# Sheet1.net
KiCad netlist of a schematic drawn in Altium Designer
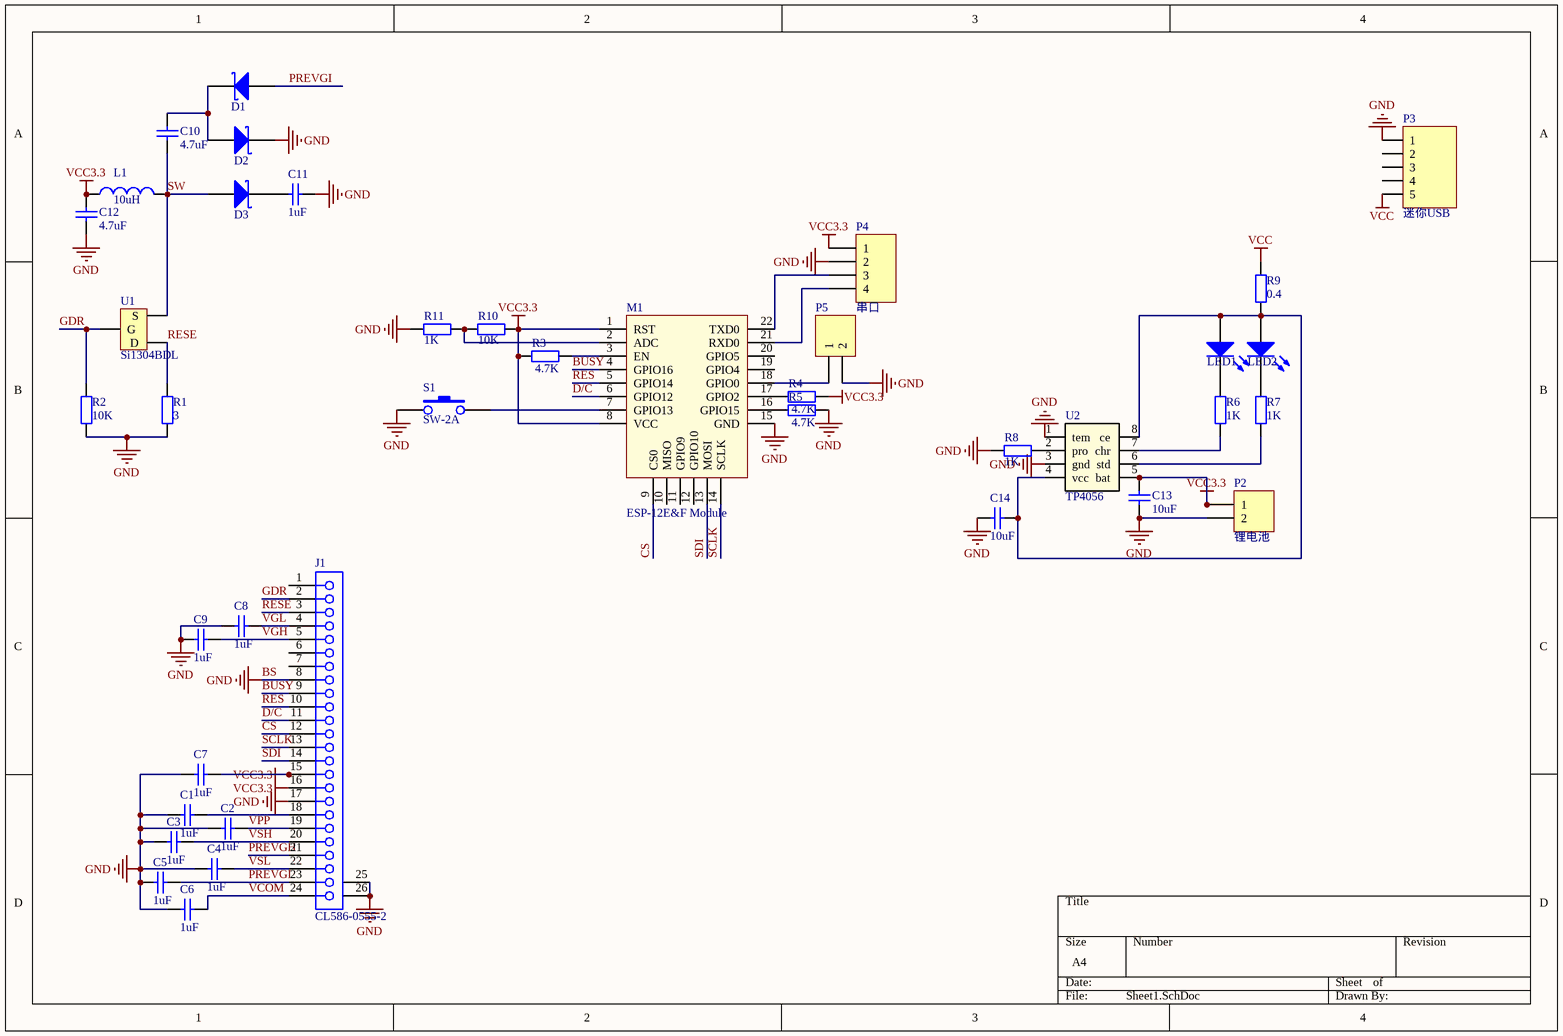
[diagram p0: Sheet1.SchDoc]

(export (version "E")
  (design (tool "Eeschema 10.0.6"))
  (components
    (comp (ref "C1")
      (value "1uF")
      (footprint "0805C")
      (description "Capacitor")
      (fields (field (name "Comment") "无极性电容") (field (name "PUBLISHER") "Altium Limited"))
      (libsource (lib "Integrated_Library1") (part "无极性电容"))
    )
    (comp (ref "C2")
      (value "1uF")
      (footprint "0805C")
      (description "Capacitor")
      (fields (field (name "Comment") "无极性电容") (field (name "PUBLISHER") "Altium Limited"))
      (libsource (lib "Integrated_Library1") (part "无极性电容"))
    )
    (comp (ref "C3")
      (value "1uF")
      (footprint "0805C")
      (description "Capacitor")
      (fields (field (name "Comment") "无极性电容") (field (name "PUBLISHER") "Altium Limited"))
      (libsource (lib "Integrated_Library1") (part "无极性电容"))
    )
    (comp (ref "C4")
      (value "1uF")
      (footprint "0805C")
      (description "Capacitor")
      (fields (field (name "Comment") "无极性电容") (field (name "PUBLISHER") "Altium Limited"))
      (libsource (lib "Integrated_Library1") (part "无极性电容"))
    )
    (comp (ref "C5")
      (value "1uF")
      (footprint "0805C")
      (description "Capacitor")
      (fields (field (name "Comment") "无极性电容") (field (name "PUBLISHER") "Altium Limited"))
      (libsource (lib "Integrated_Library1") (part "无极性电容"))
    )
    (comp (ref "C6")
      (value "1uF")
      (footprint "0805C")
      (description "Capacitor")
      (fields (field (name "Comment") "无极性电容") (field (name "PUBLISHER") "Altium Limited"))
      (libsource (lib "Integrated_Library1") (part "无极性电容"))
    )
    (comp (ref "C7")
      (value "1uF")
      (footprint "0805C")
      (description "Capacitor")
      (fields (field (name "Comment") "无极性电容") (field (name "PUBLISHER") "Altium Limited"))
      (libsource (lib "Integrated_Library1") (part "无极性电容"))
    )
    (comp (ref "C8")
      (value "1uF")
      (footprint "0805C")
      (description "Capacitor")
      (fields (field (name "Comment") "无极性电容") (field (name "PUBLISHER") "Altium Limited"))
      (libsource (lib "Integrated_Library1") (part "无极性电容"))
    )
    (comp (ref "C9")
      (value "1uF")
      (footprint "0805C")
      (description "Capacitor")
      (fields (field (name "Comment") "无极性电容") (field (name "PUBLISHER") "Altium Limited"))
      (libsource (lib "Integrated_Library1") (part "无极性电容"))
    )
    (comp (ref "C10")
      (value "4.7uF")
      (footprint "0805C")
      (description "Capacitor")
      (fields (field (name "Comment") "无极性电容") (field (name "PUBLISHER") "Altium Limited"))
      (libsource (lib "Integrated_Library1") (part "无极性电容"))
    )
    (comp (ref "C11")
      (value "1uF")
      (footprint "0805C")
      (description "Capacitor")
      (fields (field (name "Comment") "无极性电容") (field (name "PUBLISHER") "Altium Limited"))
      (libsource (lib "Integrated_Library1") (part "无极性电容"))
    )
    (comp (ref "C12")
      (value "4.7uF")
      (footprint "0805C")
      (description "Capacitor")
      (fields (field (name "Comment") "无极性电容") (field (name "PUBLISHER") "Altium Limited"))
      (libsource (lib "Integrated_Library1") (part "无极性电容"))
    )
    (comp (ref "C13")
      (value "10uF")
      (footprint "0805C")
      (description "Capacitor")
      (fields (field (name "Comment") "无极性电容") (field (name "PUBLISHER") "Altium Limited"))
      (libsource (lib "Integrated_Library1") (part "无极性电容"))
    )
    (comp (ref "C14")
      (value "10uF")
      (footprint "0805C")
      (description "Capacitor")
      (fields (field (name "Comment") "无极性电容") (field (name "PUBLISHER") "Altium Limited"))
      (libsource (lib "Integrated_Library1") (part "无极性电容"))
    )
    (comp (ref "D1")
      (value "1N5817-肖特基二极管_1")
      (footprint "SOD123")
      (libsource (lib "Integrated_Library1") (part "1N5817-肖特基二极管_1"))
    )
    (comp (ref "D2")
      (value "1N5817-肖特基二极管_1")
      (footprint "SOD123")
      (libsource (lib "Integrated_Library1") (part "1N5817-肖特基二极管_1"))
    )
    (comp (ref "D3")
      (value "1N5817-肖特基二极管_1")
      (footprint "SOD123")
      (libsource (lib "Integrated_Library1") (part "1N5817-肖特基二极管_1"))
    )
    (comp (ref "J1")
      (value "CL586-0555-2")
      (footprint "FH12-24S-0.5SH")
      (description "FH12 Series, \"Flip-Lock\" SMT/ZIF Connector - 0.5mm Spaced Top Contact")
      (fields (field (name "PUBLISHER") "Altium Limited"))
      (libsource (lib "HRS FPC-FFC FH12 Series") (part "CL586-0555-2"))
    )
    (comp (ref "L1")
      (value "10uH")
      (footprint "CAPM-B-3528X21N")
      (description "Inductor")
      (fields (field (name "PUBLISHER") "Altium Limited"))
      (libsource (lib "Integrated_Library1") (part "Inductor"))
    )
    (comp (ref "LED1")
      (value "LED-贴片-直插")
      (footprint "LED_0805")
      (libsource (lib "Integrated_Library1") (part "LED-贴片-直插"))
    )
    (comp (ref "LED2")
      (value "LED-贴片-直插")
      (footprint "LED_0805")
      (libsource (lib "Integrated_Library1") (part "LED-贴片-直插"))
    )
    (comp (ref "M1")
      (value "ESP-12E&F Module")
      (footprint "ESP-12E&F Module")
      (libsource (lib "ESP-12E&F Module") (part "ESP-12E&F Module"))
    )
    (comp (ref "P2")
      (value "锂电池")
      (footprint "HDR1X2")
      (description "Header, 2-Pin")
      (fields (field (name "PUBLISHER") "Altium Limited"))
      (libsource (lib "Miscellaneous Connectors") (part "Header 2"))
    )
    (comp (ref "P3") (value "迷你USB") (footprint "迷你usb") (libsource (lib "wodeku") (part "迷你USB")))
    (comp (ref "P4")
      (value "串口")
      (footprint "HDR1X4")
      (description "Header, 4-Pin")
      (fields (field (name "PUBLISHER") "Altium Limited"))
      (libsource (lib "Miscellaneous Connectors") (part "Header 4"))
    )
    (comp (ref "P5")
      (value "~")
      (footprint "HDR1X2")
      (description "Header, 2-Pin")
      (fields (field (name "PUBLISHER") "Altium Limited"))
      (libsource (lib "") (part "Header 2_1"))
    )
    (comp (ref "R1")
      (value "3")
      (footprint "0805R")
      (description "Resistor")
      (fields (field (name "Comment") "贴片电阻") (field (name "PUBLISHER") "Altium Limited"))
      (libsource (lib "") (part "贴片电阻_3"))
    )
    (comp (ref "R2")
      (value "10K")
      (footprint "0805R")
      (description "Resistor")
      (fields (field (name "Comment") "贴片电阻") (field (name "PUBLISHER") "Altium Limited"))
      (libsource (lib "") (part "贴片电阻_3"))
    )
    (comp (ref "R3")
      (value "4.7K")
      (footprint "0805R")
      (description "Resistor")
      (fields (field (name "Comment") "贴片电阻") (field (name "PUBLISHER") "Altium Limited"))
      (libsource (lib "Integrated_Library1") (part "贴片电阻"))
    )
    (comp (ref "R4")
      (value "4.7K")
      (footprint "0805R")
      (description "Resistor")
      (fields (field (name "Comment") "贴片电阻") (field (name "PUBLISHER") "Altium Limited"))
      (libsource (lib "Integrated_Library1") (part "贴片电阻"))
    )
    (comp (ref "R5")
      (value "4.7K")
      (footprint "0805R")
      (description "Resistor")
      (fields (field (name "Comment") "贴片电阻") (field (name "PUBLISHER") "Altium Limited"))
      (libsource (lib "Integrated_Library1") (part "贴片电阻"))
    )
    (comp (ref "R6")
      (value "1K")
      (footprint "0805R")
      (description "Resistor")
      (fields (field (name "Comment") "贴片电阻") (field (name "PUBLISHER") "Altium Limited"))
      (libsource (lib "") (part "贴片电阻_2"))
    )
    (comp (ref "R7")
      (value "1K")
      (footprint "0805R")
      (description "Resistor")
      (fields (field (name "Comment") "贴片电阻") (field (name "PUBLISHER") "Altium Limited"))
      (libsource (lib "") (part "贴片电阻_2"))
    )
    (comp (ref "R8")
      (value "1K")
      (footprint "0805R")
      (description "Resistor")
      (fields (field (name "Comment") "贴片电阻") (field (name "PUBLISHER") "Altium Limited"))
      (libsource (lib "") (part "贴片电阻_1"))
    )
    (comp (ref "R9")
      (value "0.4")
      (footprint "0805R")
      (description "Resistor")
      (fields (field (name "Comment") "贴片电阻") (field (name "PUBLISHER") "Altium Limited"))
      (libsource (lib "") (part "贴片电阻_3"))
    )
    (comp (ref "R10")
      (value "10K")
      (footprint "0805R")
      (description "Resistor")
      (fields (field (name "Comment") "贴片电阻") (field (name "PUBLISHER") "Altium Limited"))
      (libsource (lib "") (part "贴片电阻_1"))
    )
    (comp (ref "R11")
      (value "1K")
      (footprint "0805R")
      (description "Resistor")
      (fields (field (name "Comment") "贴片电阻") (field (name "PUBLISHER") "Altium Limited"))
      (libsource (lib "") (part "贴片电阻_1"))
    )
    (comp (ref "S1")
      (value "SW-2A")
      (footprint "SW贴片-3*6*2.5")
      (libsource (lib "Integrated_Library1") (part "SW-2A"))
    )
    (comp (ref "U1") (value "Si1304BDL") (footprint "AO3400") (libsource (lib "wodeku") (part "AO3400")))
    (comp (ref "U2") (value "TP4056") (footprint "SOP8LM386") (libsource (lib "TP4056") (part "TP4056")))
  )
  (nets
    (net (code "1") (name "/BUSY") (class "Default")
      (node (ref "J1") (pin "9") (pinfunction "9_9") (pintype "passive"))
      (node (ref "M1") (pin "4") (pinfunction "GPIO16_4") (pintype "passive"))
    )
    (net (code "2") (name "/CS") (class "Default")
      (node (ref "J1") (pin "12") (pinfunction "12_12") (pintype "passive"))
      (node (ref "M1") (pin "9") (pinfunction "CS0_9") (pintype "passive"))
    )
    (net (code "3") (name "/D{slash}C") (class "Default")
      (node (ref "J1") (pin "11") (pinfunction "11_11") (pintype "passive"))
      (node (ref "M1") (pin "6") (pinfunction "GPIO12_6") (pintype "passive"))
    )
    (net (code "4") (name "/GDR") (class "Default")
      (node (ref "J1") (pin "2") (pinfunction "2_2") (pintype "passive"))
      (node (ref "R2") (pin "2") (pinfunction "2_2") (pintype "passive"))
      (node (ref "U1") (pin "1") (pinfunction "G_1") (pintype "passive"))
    )
    (net (code "5") (name "/PREVGH") (class "Default")
      (node (ref "J1") (pin "21") (pinfunction "21_21") (pintype "passive"))
    )
    (net (code "6") (name "/PREVGI") (class "Default")
      (node (ref "C5") (pin "2") (pinfunction "2_2") (pintype "passive"))
      (node (ref "D1") (pin "1") (pinfunction "A_1") (pintype "passive"))
      (node (ref "J1") (pin "23") (pinfunction "23_23") (pintype "passive"))
    )
    (net (code "7") (name "/RES") (class "Default")
      (node (ref "J1") (pin "10") (pinfunction "10_10") (pintype "passive"))
      (node (ref "M1") (pin "5") (pinfunction "GPIO14_5") (pintype "passive"))
    )
    (net (code "8") (name "/RESE") (class "Default")
      (node (ref "J1") (pin "3") (pinfunction "3_3") (pintype "passive"))
      (node (ref "R1") (pin "2") (pinfunction "2_2") (pintype "passive"))
      (node (ref "U1") (pin "3") (pinfunction "D_3") (pintype "passive"))
    )
    (net (code "9") (name "/SCLK") (class "Default")
      (node (ref "J1") (pin "13") (pinfunction "13_13") (pintype "passive"))
      (node (ref "M1") (pin "14") (pinfunction "SCLK_14") (pintype "passive"))
    )
    (net (code "10") (name "/SDI") (class "Default")
      (node (ref "J1") (pin "14") (pinfunction "14_14") (pintype "passive"))
      (node (ref "M1") (pin "13") (pinfunction "MOSI_13") (pintype "passive"))
    )
    (net (code "11") (name "/SW") (class "Default")
      (node (ref "C10") (pin "1") (pinfunction "1_1") (pintype "passive"))
      (node (ref "D3") (pin "1") (pinfunction "A_1") (pintype "passive"))
      (node (ref "L1") (pin "2") (pinfunction "2_2") (pintype "passive"))
      (node (ref "U1") (pin "2") (pinfunction "S_2") (pintype "passive"))
    )
    (net (code "12") (name "/VCOM") (class "Default")
      (node (ref "C6") (pin "2") (pinfunction "2_2") (pintype "passive"))
      (node (ref "J1") (pin "24") (pinfunction "24_24") (pintype "passive"))
    )
    (net (code "13") (name "/VGH") (class "Default")
      (node (ref "C9") (pin "2") (pinfunction "2_2") (pintype "passive"))
      (node (ref "J1") (pin "5") (pinfunction "5_5") (pintype "passive"))
    )
    (net (code "14") (name "/VGL") (class "Default")
      (node (ref "C8") (pin "2") (pinfunction "2_2") (pintype "passive"))
      (node (ref "J1") (pin "4") (pinfunction "4_4") (pintype "passive"))
    )
    (net (code "15") (name "/VPP") (class "Default")
      (node (ref "C2") (pin "2") (pinfunction "2_2") (pintype "passive"))
      (node (ref "J1") (pin "19") (pinfunction "19_19") (pintype "passive"))
    )
    (net (code "16") (name "/VSH") (class "Default")
      (node (ref "C3") (pin "2") (pinfunction "2_2") (pintype "passive"))
      (node (ref "J1") (pin "20") (pinfunction "20_20") (pintype "passive"))
    )
    (net (code "17") (name "/VSL") (class "Default")
      (node (ref "C4") (pin "2") (pinfunction "2_2") (pintype "passive"))
      (node (ref "J1") (pin "22") (pinfunction "22_22") (pintype "passive"))
    )
    (net (code "18") (name "GND") (class "Default")
      (node (ref "C1") (pin "1") (pinfunction "1_1") (pintype "passive"))
      (node (ref "C11") (pin "1") (pinfunction "1_1") (pintype "passive"))
      (node (ref "C12") (pin "1") (pinfunction "1_1") (pintype "passive"))
      (node (ref "C13") (pin "1") (pinfunction "1_1") (pintype "passive"))
      (node (ref "C14") (pin "2") (pinfunction "2_2") (pintype "passive"))
      (node (ref "C2") (pin "1") (pinfunction "1_1") (pintype "passive"))
      (node (ref "C3") (pin "1") (pinfunction "1_1") (pintype "passive"))
      (node (ref "C4") (pin "1") (pinfunction "1_1") (pintype "passive"))
      (node (ref "C5") (pin "1") (pinfunction "1_1") (pintype "passive"))
      (node (ref "C6") (pin "1") (pinfunction "1_1") (pintype "passive"))
      (node (ref "C7") (pin "1") (pinfunction "1_1") (pintype "passive"))
      (node (ref "C8") (pin "1") (pinfunction "1_1") (pintype "passive"))
      (node (ref "C9") (pin "1") (pinfunction "1_1") (pintype "passive"))
      (node (ref "D2") (pin "2") (pinfunction "K_2") (pintype "passive"))
      (node (ref "J1") (pin "17") (pinfunction "17_17") (pintype "passive"))
      (node (ref "J1") (pin "25") (pinfunction "MH1_25") (pintype "passive"))
      (node (ref "J1") (pin "26") (pinfunction "MH2_26") (pintype "passive"))
      (node (ref "J1") (pin "8") (pinfunction "8_8") (pintype "passive"))
      (node (ref "M1") (pin "15") (pinfunction "GND_15") (pintype "passive"))
      (node (ref "P2") (pin "2") (pinfunction "2_2") (pintype "passive"))
      (node (ref "P3") (pin "1") (pinfunction "1_1") (pintype "passive"))
      (node (ref "P4") (pin "2") (pinfunction "2_2") (pintype "passive"))
      (node (ref "P5") (pin "2") (pinfunction "2_2") (pintype "passive"))
      (node (ref "R1") (pin "1") (pinfunction "1_1") (pintype "passive"))
      (node (ref "R11") (pin "1") (pinfunction "1_1") (pintype "passive"))
      (node (ref "R2") (pin "1") (pinfunction "1_1") (pintype "passive"))
      (node (ref "R5") (pin "1") (pinfunction "1_1") (pintype "passive"))
      (node (ref "R8") (pin "1") (pinfunction "1_1") (pintype "passive"))
      (node (ref "S1") (pin "1") (pinfunction "1_1") (pintype "passive"))
      (node (ref "U2") (pin "1") (pinfunction "tem_1") (pintype "passive"))
      (node (ref "U2") (pin "3") (pinfunction "gnd_3") (pintype "passive"))
    )
    (net (code "19") (name "Net-(C1-Pad2)") (class "Default")
      (node (ref "C1") (pin "2") (pinfunction "2_2") (pintype "passive"))
      (node (ref "J1") (pin "18") (pinfunction "18_18") (pintype "passive"))
    )
    (net (code "20") (name "Net-(D1-K)") (class "Default")
      (node (ref "C10") (pin "2") (pinfunction "2_2") (pintype "passive"))
      (node (ref "D1") (pin "2") (pinfunction "K_2") (pintype "passive"))
      (node (ref "D2") (pin "1") (pinfunction "A_1") (pintype "passive"))
    )
    (net (code "21") (name "Net-(D3-K)") (class "Default")
      (node (ref "C11") (pin "2") (pinfunction "2_2") (pintype "passive"))
      (node (ref "D3") (pin "2") (pinfunction "K_2") (pintype "passive"))
    )
    (net (code "22") (name "Net-(LED1-A)") (class "Default")
      (node (ref "C14") (pin "1") (pinfunction "1_1") (pintype "passive"))
      (node (ref "LED1") (pin "1") (pinfunction "A_1") (pintype "passive"))
      (node (ref "LED2") (pin "1") (pinfunction "A_1") (pintype "passive"))
      (node (ref "R9") (pin "1") (pinfunction "1_1") (pintype "passive"))
      (node (ref "U2") (pin "4") (pinfunction "vcc_4") (pintype "passive"))
      (node (ref "U2") (pin "8") (pinfunction "ce_8") (pintype "passive"))
    )
    (net (code "23") (name "Net-(LED1-K)") (class "Default")
      (node (ref "LED1") (pin "2") (pinfunction "K_2") (pintype "passive"))
      (node (ref "R6") (pin "1") (pinfunction "1_1") (pintype "passive"))
    )
    (net (code "24") (name "Net-(LED2-K)") (class "Default")
      (node (ref "LED2") (pin "2") (pinfunction "K_2") (pintype "passive"))
      (node (ref "R7") (pin "1") (pinfunction "1_1") (pintype "passive"))
    )
    (net (code "25") (name "Net-(M1-ADC)") (class "Default")
      (node (ref "M1") (pin "2") (pinfunction "ADC_2") (pintype "passive"))
      (node (ref "R10") (pin "1") (pinfunction "1_1") (pintype "passive"))
      (node (ref "R11") (pin "2") (pinfunction "2_2") (pintype "passive"))
    )
    (net (code "26") (name "Net-(M1-EN)") (class "Default")
      (node (ref "M1") (pin "3") (pinfunction "EN_3") (pintype "passive"))
      (node (ref "R3") (pin "1") (pinfunction "1_1") (pintype "passive"))
    )
    (net (code "27") (name "Net-(M1-GPIO0)") (class "Default")
      (node (ref "M1") (pin "18") (pinfunction "GPIO0_18") (pintype "passive"))
      (node (ref "P5") (pin "1") (pinfunction "1_1") (pintype "passive"))
    )
    (net (code "28") (name "Net-(M1-GPIO2)") (class "Default")
      (node (ref "M1") (pin "17") (pinfunction "GPIO2_17") (pintype "passive"))
      (node (ref "R4") (pin "2") (pinfunction "2_2") (pintype "passive"))
    )
    (net (code "29") (name "Net-(M1-GPIO13)") (class "Default")
      (node (ref "M1") (pin "7") (pinfunction "GPIO13_7") (pintype "passive"))
      (node (ref "S1") (pin "2") (pinfunction "2_2") (pintype "passive"))
    )
    (net (code "30") (name "Net-(M1-GPIO15)") (class "Default")
      (node (ref "M1") (pin "16") (pinfunction "GPIO15_16") (pintype "passive"))
      (node (ref "R5") (pin "2") (pinfunction "2_2") (pintype "passive"))
    )
    (net (code "31") (name "Net-(M1-RXD0)") (class "Default")
      (node (ref "M1") (pin "21") (pinfunction "RXD0_21") (pintype "passive"))
      (node (ref "P4") (pin "4") (pinfunction "4_4") (pintype "passive"))
    )
    (net (code "32") (name "Net-(M1-TXD0)") (class "Default")
      (node (ref "M1") (pin "22") (pinfunction "TXD0_22") (pintype "passive"))
      (node (ref "P4") (pin "3") (pinfunction "3_3") (pintype "passive"))
    )
    (net (code "33") (name "Net-(U2-chr)") (class "Default")
      (node (ref "R6") (pin "2") (pinfunction "2_2") (pintype "passive"))
      (node (ref "U2") (pin "7") (pinfunction "chr_7") (pintype "passive"))
    )
    (net (code "34") (name "Net-(U2-pro)") (class "Default")
      (node (ref "R8") (pin "2") (pinfunction "2_2") (pintype "passive"))
      (node (ref "U2") (pin "2") (pinfunction "pro_2") (pintype "passive"))
    )
    (net (code "35") (name "Net-(U2-std)") (class "Default")
      (node (ref "R7") (pin "2") (pinfunction "2_2") (pintype "passive"))
      (node (ref "U2") (pin "6") (pinfunction "std_6") (pintype "passive"))
    )
    (net (code "36") (name "VCC") (class "Default")
      (node (ref "P3") (pin "5") (pinfunction "5_5") (pintype "passive"))
      (node (ref "R9") (pin "2") (pinfunction "2_2") (pintype "passive"))
    )
    (net (code "37") (name "VCC3.3") (class "Default")
      (node (ref "C12") (pin "2") (pinfunction "2_2") (pintype "passive"))
      (node (ref "C13") (pin "2") (pinfunction "2_2") (pintype "passive"))
      (node (ref "C7") (pin "2") (pinfunction "2_2") (pintype "passive"))
      (node (ref "J1") (pin "15") (pinfunction "15_15") (pintype "passive"))
      (node (ref "J1") (pin "16") (pinfunction "16_16") (pintype "passive"))
      (node (ref "L1") (pin "1") (pinfunction "1_1") (pintype "passive"))
      (node (ref "M1") (pin "1") (pinfunction "RST_1") (pintype "passive"))
      (node (ref "M1") (pin "8") (pinfunction "VCC_8") (pintype "passive"))
      (node (ref "P2") (pin "1") (pinfunction "1_1") (pintype "passive"))
      (node (ref "P4") (pin "1") (pinfunction "1_1") (pintype "passive"))
      (node (ref "R10") (pin "2") (pinfunction "2_2") (pintype "passive"))
      (node (ref "R3") (pin "2") (pinfunction "2_2") (pintype "passive"))
      (node (ref "R4") (pin "1") (pinfunction "1_1") (pintype "passive"))
      (node (ref "U2") (pin "5") (pinfunction "bat_5") (pintype "passive"))
    )
    (net (code "38") (name "unconnected-(J1-Pad1)") (class "Default")
      (node (ref "J1") (pin "1") (pinfunction "1_1") (pintype "passive"))
    )
    (net (code "39") (name "unconnected-(J1-Pad6)") (class "Default")
      (node (ref "J1") (pin "6") (pinfunction "6_6") (pintype "passive"))
    )
    (net (code "40") (name "unconnected-(J1-Pad7)") (class "Default")
      (node (ref "J1") (pin "7") (pinfunction "7_7") (pintype "passive"))
    )
    (net (code "41") (name "unconnected-(M1-GPIO4-Pad19)") (class "Default")
      (node (ref "M1") (pin "19") (pinfunction "GPIO4_19") (pintype "passive"))
    )
    (net (code "42") (name "unconnected-(M1-GPIO5-Pad20)") (class "Default")
      (node (ref "M1") (pin "20") (pinfunction "GPIO5_20") (pintype "passive"))
    )
    (net (code "43") (name "unconnected-(M1-GPIO9-Pad11)") (class "Default")
      (node (ref "M1") (pin "11") (pinfunction "GPIO9_11") (pintype "passive"))
    )
    (net (code "44") (name "unconnected-(M1-GPIO10-Pad12)") (class "Default")
      (node (ref "M1") (pin "12") (pinfunction "GPIO10_12") (pintype "passive"))
    )
    (net (code "45") (name "unconnected-(M1-MISO-Pad10)") (class "Default")
      (node (ref "M1") (pin "10") (pinfunction "MISO_10") (pintype "passive"))
    )
    (net (code "46") (name "unconnected-(P3-Pad2)") (class "Default")
      (node (ref "P3") (pin "2") (pinfunction "2_2") (pintype "passive"))
    )
    (net (code "47") (name "unconnected-(P3-Pad3)") (class "Default")
      (node (ref "P3") (pin "3") (pinfunction "3_3") (pintype "passive"))
    )
    (net (code "48") (name "unconnected-(P3-Pad4)") (class "Default")
      (node (ref "P3") (pin "4") (pinfunction "4_4") (pintype "passive"))
    )
  )
)
